# ESP_Board.net
KiCad netlist of a schematic drawn in Altium Designer
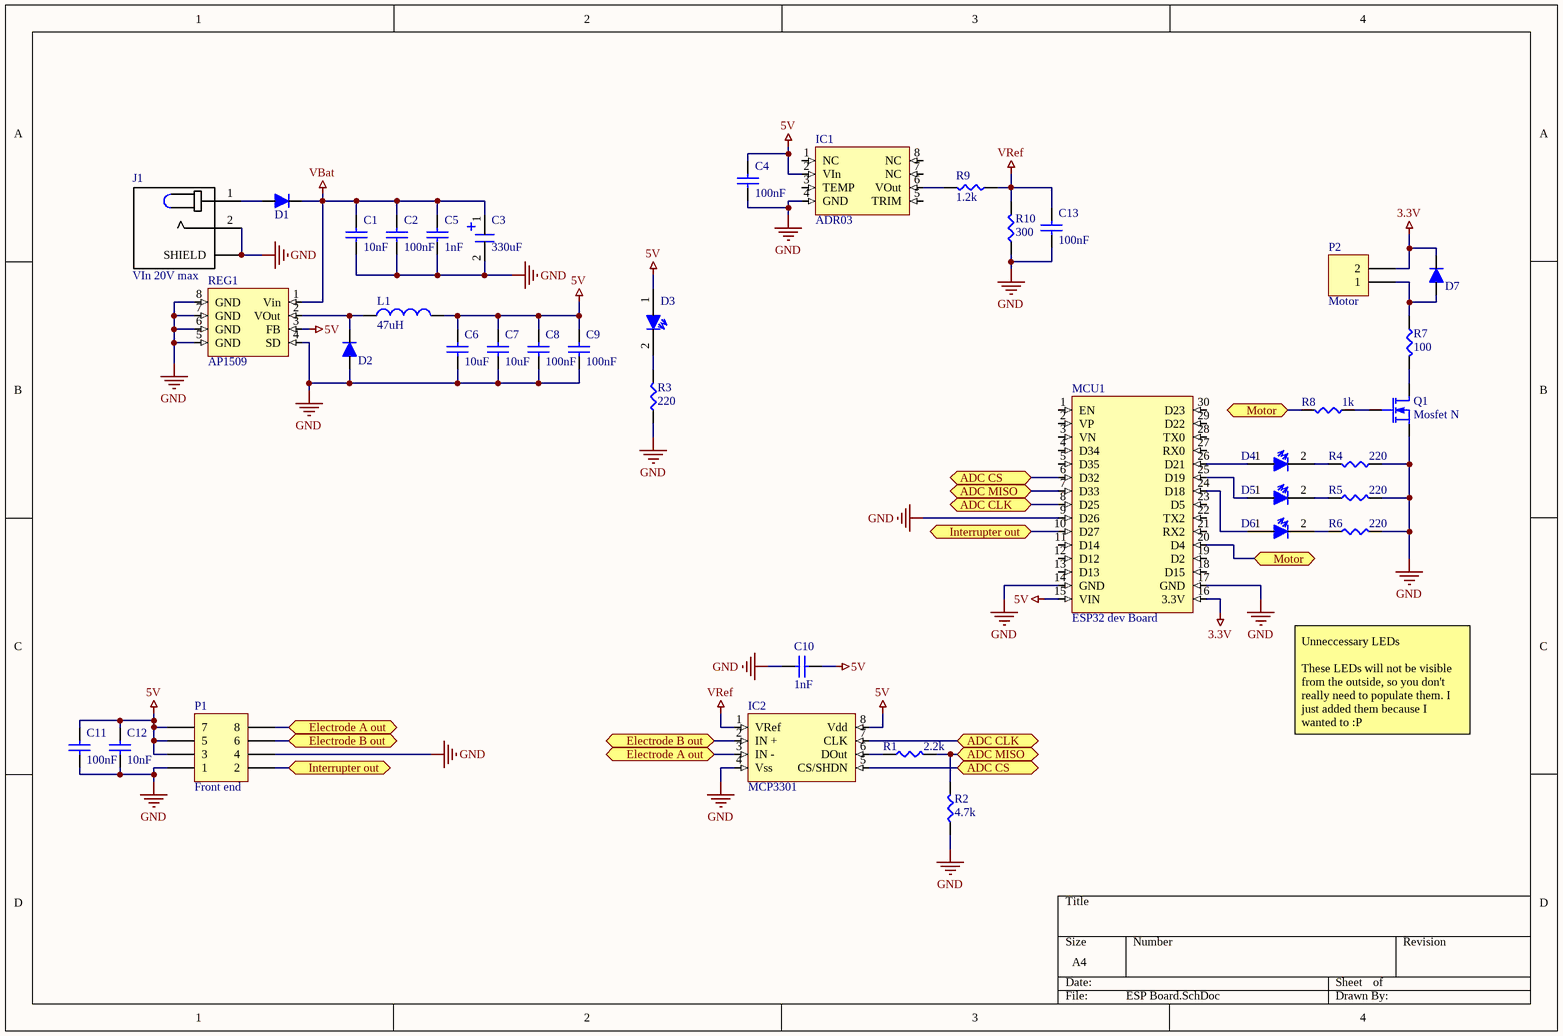
[diagram p0: ESP Board.SchDoc]

(export (version "E")
  (design (tool "Eeschema 10.0.6"))
  (components
    (comp (ref "C1") (value "10nF") (footprint "0805") (libsource (lib "stdLib") (part "Cap")))
    (comp (ref "C2") (value "100nF") (footprint "0805") (libsource (lib "stdLib") (part "Cap")))
    (comp (ref "C3")
      (value "330uF")
      (footprint "ESL476M100AH9AA")
      (libsource (lib "stdLib") (part "Cap Polar"))
    )
    (comp (ref "C4") (value "100nF") (footprint "0805") (libsource (lib "stdLib") (part "Cap")))
    (comp (ref "C5") (value "1nF") (footprint "0805") (libsource (lib "stdLib") (part "Cap")))
    (comp (ref "C6") (value "10uF") (footprint "0805") (libsource (lib "stdLib") (part "Cap")))
    (comp (ref "C7") (value "10uF") (footprint "0805") (libsource (lib "stdLib") (part "Cap")))
    (comp (ref "C8") (value "100nF") (footprint "0805") (libsource (lib "stdLib") (part "Cap")))
    (comp (ref "C9") (value "100nF") (footprint "0805") (libsource (lib "stdLib") (part "Cap")))
    (comp (ref "C10") (value "1nF") (footprint "0805") (libsource (lib "stdLib") (part "Cap")))
    (comp (ref "C11") (value "100nF") (footprint "0805") (libsource (lib "stdLib") (part "Cap")))
    (comp (ref "C12") (value "10nF") (footprint "0805") (libsource (lib "stdLib") (part "Cap")))
    (comp (ref "C13") (value "100nF") (footprint "0805") (libsource (lib "stdLib") (part "Cap")))
    (comp (ref "D1")
      (value "Diode")
      (footprint "DO-214")
      (description "Cmon its a diode what more do I need to say?")
      (libsource (lib "stdLib") (part "Diode"))
    )
    (comp (ref "D2")
      (value "Diode")
      (footprint "DO-214")
      (description "Cmon its a diode what more do I need to say?")
      (libsource (lib "stdLib") (part "Diode"))
    )
    (comp (ref "D3") (value "Power") (footprint "0805") (libsource (lib "stdLib") (part "LED")))
    (comp (ref "D4") (value "NOP") (footprint "0805") (libsource (lib "stdLib") (part "LED")))
    (comp (ref "D5") (value "NOP") (footprint "0805") (libsource (lib "stdLib") (part "LED")))
    (comp (ref "D6") (value "NOP") (footprint "0805") (libsource (lib "stdLib") (part "LED")))
    (comp (ref "D7")
      (value "Diode")
      (footprint "DO-214")
      (description "Cmon its a diode what more do I need to say?")
      (libsource (lib "stdLib") (part "Diode"))
    )
    (comp (ref "IC1")
      (value "ADR03")
      (footprint "SOIC8")
      (description "Precision voltage reference 0.1%")
      (libsource (lib "stdLib") (part "ADR0X"))
    )
    (comp (ref "IC2")
      (value "MCP3301")
      (footprint "SOIC8")
      (description "13 bit differential ADC")
      (libsource (lib "stdLib") (part "MCP3301"))
    )
    (comp (ref "J1")
      (value "VIn 20V max")
      (footprint "PJ-082BH")
      (libsource (lib "stdLib") (part "Barrel Power Plug"))
    )
    (comp (ref "L1")
      (value "47uH")
      (footprint "1812 Low density")
      (libsource (lib "stdLib") (part "Inductor"))
    )
    (comp (ref "MCU1")
      (value "ESP32 dev Board")
      (footprint "ESP32 dev board")
      (description "Dev board of the esp32")
      (libsource (lib "stdLib") (part "ESP32 dev Board"))
    )
    (comp (ref "P1")
      (value "Front end")
      (footprint "HDR2X4")
      (description "Header, 4-Pin, Dual row")
      (fields (field (name "PUBLISHER") "Altium Limited"))
      (libsource (lib "Miscellaneous Connectors") (part "Header 4X2"))
    )
    (comp (ref "P2")
      (value "Motor")
      (footprint "XH2")
      (description "Header, 2-Pin")
      (fields (field (name "PUBLISHER") "Altium Limited"))
      (libsource (lib "Miscellaneous Connectors") (part "Header 2"))
    )
    (comp (ref "Q1") (value "Mosfet N") (footprint "sot 23") (libsource (lib "stdLib") (part "Mosfet N")))
    (comp (ref "R1") (value "2.2k") (footprint "0805") (libsource (lib "stdLib") (part "Resistor")))
    (comp (ref "R2") (value "4.7k") (footprint "0805") (libsource (lib "stdLib") (part "Resistor")))
    (comp (ref "R3") (value "220") (footprint "0805") (libsource (lib "stdLib") (part "Resistor")))
    (comp (ref "R4") (value "220") (footprint "0805") (libsource (lib "stdLib") (part "Resistor")))
    (comp (ref "R5") (value "220") (footprint "0805") (libsource (lib "stdLib") (part "Resistor")))
    (comp (ref "R6") (value "220") (footprint "0805") (libsource (lib "stdLib") (part "Resistor")))
    (comp (ref "R7") (value "100") (footprint "0805") (libsource (lib "stdLib") (part "Resistor")))
    (comp (ref "R8") (value "1k") (footprint "0805") (libsource (lib "stdLib") (part "Resistor")))
    (comp (ref "R9") (value "1.2k") (footprint "0805") (libsource (lib "stdLib") (part "Resistor")))
    (comp (ref "R10") (value "300") (footprint "0805") (libsource (lib "stdLib") (part "Resistor")))
    (comp (ref "REG1")
      (value "AP1509")
      (footprint "SOIC8")
      (description "Fixed voltage buck regulator")
      (libsource (lib "stdLib") (part "AP1509"))
    )
  )
  (nets
    (net (code "1") (name "/ADC CLK") (class "Default")
      (node (ref "IC2") (pin "7") (pinfunction "CLK_7") (pintype "input"))
      (node (ref "MCU1") (pin "8") (pinfunction "D25_8") (pintype "input"))
    )
    (net (code "2") (name "/ADC CS") (class "Default")
      (node (ref "IC2") (pin "5") (pinfunction "CS/SHDN_5") (pintype "input"))
      (node (ref "MCU1") (pin "6") (pinfunction "D32_6") (pintype "input"))
    )
    (net (code "3") (name "/ADC MISO") (class "Default")
      (node (ref "MCU1") (pin "7") (pinfunction "D33_7") (pintype "input"))
      (node (ref "R1") (pin "2") (pinfunction "2_2") (pintype "passive"))
      (node (ref "R2") (pin "2") (pinfunction "2_2") (pintype "passive"))
    )
    (net (code "4") (name "/Electrode A out") (class "Default")
      (node (ref "IC2") (pin "3") (pinfunction "IN_-_3") (pintype "input"))
      (node (ref "P1") (pin "8") (pinfunction "8_8") (pintype "passive"))
    )
    (net (code "5") (name "/Electrode B out") (class "Default")
      (node (ref "IC2") (pin "2") (pinfunction "IN_+_2") (pintype "input"))
      (node (ref "P1") (pin "6") (pinfunction "6_6") (pintype "passive"))
    )
    (net (code "6") (name "/Interrupter out") (class "Default")
      (node (ref "MCU1") (pin "10") (pinfunction "D27_10") (pintype "input"))
      (node (ref "P1") (pin "2") (pinfunction "2_2") (pintype "passive"))
    )
    (net (code "7") (name "/Motor") (class "Default")
      (node (ref "MCU1") (pin "20") (pinfunction "D4_20") (pintype "input"))
      (node (ref "R8") (pin "2") (pinfunction "2_2") (pintype "passive"))
    )
    (net (code "8") (name "3.3V") (class "Default")
      (node (ref "D7") (pin "2") (pintype "passive"))
      (node (ref "MCU1") (pin "16") (pinfunction "3.3V_16") (pintype "input"))
      (node (ref "P2") (pin "2") (pinfunction "2_2") (pintype "passive"))
    )
    (net (code "9") (name "5V") (class "Default")
      (node (ref "C10") (pin "2") (pinfunction "2_2") (pintype "passive"))
      (node (ref "C11") (pin "2") (pinfunction "2_2") (pintype "passive"))
      (node (ref "C12") (pin "2") (pinfunction "2_2") (pintype "passive"))
      (node (ref "C4") (pin "2") (pinfunction "2_2") (pintype "passive"))
      (node (ref "C6") (pin "1") (pinfunction "1_1") (pintype "passive"))
      (node (ref "C7") (pin "1") (pinfunction "1_1") (pintype "passive"))
      (node (ref "C8") (pin "1") (pinfunction "1_1") (pintype "passive"))
      (node (ref "C9") (pin "1") (pinfunction "1_1") (pintype "passive"))
      (node (ref "D3") (pin "1") (pintype "passive"))
      (node (ref "IC1") (pin "2") (pinfunction "VIn_2") (pintype "input"))
      (node (ref "IC2") (pin "8") (pinfunction "Vdd_8") (pintype "input"))
      (node (ref "L1") (pin "1") (pinfunction "1_1") (pintype "passive"))
      (node (ref "MCU1") (pin "15") (pinfunction "VIN_15") (pintype "input"))
      (node (ref "P1") (pin "3") (pinfunction "3_3") (pintype "passive"))
      (node (ref "P1") (pin "5") (pinfunction "5_5") (pintype "passive"))
      (node (ref "P1") (pin "7") (pinfunction "7_7") (pintype "passive"))
      (node (ref "REG1") (pin "3") (pinfunction "FB_3") (pintype "input"))
    )
    (net (code "10") (name "GND") (class "Default")
      (node (ref "C1") (pin "1") (pinfunction "1_1") (pintype "passive"))
      (node (ref "C10") (pin "1") (pinfunction "1_1") (pintype "passive"))
      (node (ref "C11") (pin "1") (pinfunction "1_1") (pintype "passive"))
      (node (ref "C12") (pin "1") (pinfunction "1_1") (pintype "passive"))
      (node (ref "C13") (pin "1") (pinfunction "1_1") (pintype "passive"))
      (node (ref "C2") (pin "1") (pinfunction "1_1") (pintype "passive"))
      (node (ref "C3") (pin "2") (pintype "passive"))
      (node (ref "C4") (pin "1") (pinfunction "1_1") (pintype "passive"))
      (node (ref "C5") (pin "1") (pinfunction "1_1") (pintype "passive"))
      (node (ref "C6") (pin "2") (pinfunction "2_2") (pintype "passive"))
      (node (ref "C7") (pin "2") (pinfunction "2_2") (pintype "passive"))
      (node (ref "C8") (pin "2") (pinfunction "2_2") (pintype "passive"))
      (node (ref "C9") (pin "2") (pinfunction "2_2") (pintype "passive"))
      (node (ref "D2") (pin "1") (pintype "passive"))
      (node (ref "IC1") (pin "4") (pinfunction "GND_4") (pintype "input"))
      (node (ref "IC2") (pin "4") (pinfunction "Vss_4") (pintype "input"))
      (node (ref "J1") (pin "2") (pinfunction "2_2") (pintype "passive"))
      (node (ref "J1") (pin "3") (pinfunction "SHIELD_3") (pintype "passive"))
      (node (ref "J1") (pin "4") (pinfunction "SHIELD_4") (pintype "passive"))
      (node (ref "J1") (pin "5") (pinfunction "SHIELD_5") (pintype "passive"))
      (node (ref "J1") (pin "6") (pinfunction "SHIELD_6") (pintype "passive"))
      (node (ref "MCU1") (pin "14") (pinfunction "GND_14") (pintype "input"))
      (node (ref "MCU1") (pin "17") (pinfunction "GND_17") (pintype "input"))
      (node (ref "MCU1") (pin "9") (pinfunction "D26_9") (pintype "input"))
      (node (ref "P1") (pin "1") (pinfunction "1_1") (pintype "passive"))
      (node (ref "P1") (pin "4") (pinfunction "4_4") (pintype "passive"))
      (node (ref "Q1") (pin "S") (pinfunction "S_S") (pintype "passive"))
      (node (ref "R10") (pin "1") (pinfunction "1_1") (pintype "passive"))
      (node (ref "R2") (pin "1") (pinfunction "1_1") (pintype "passive"))
      (node (ref "R3") (pin "1") (pinfunction "1_1") (pintype "passive"))
      (node (ref "R4") (pin "1") (pinfunction "1_1") (pintype "passive"))
      (node (ref "R5") (pin "2") (pinfunction "2_2") (pintype "passive"))
      (node (ref "R6") (pin "2") (pinfunction "2_2") (pintype "passive"))
      (node (ref "REG1") (pin "4") (pinfunction "SD_4") (pintype "input"))
      (node (ref "REG1") (pin "5") (pinfunction "GND_5") (pintype "input"))
      (node (ref "REG1") (pin "6") (pinfunction "GND_6") (pintype "input"))
      (node (ref "REG1") (pin "7") (pinfunction "GND_7") (pintype "input"))
      (node (ref "REG1") (pin "8") (pinfunction "GND_8") (pintype "input"))
    )
    (net (code "11") (name "Net-(D1-Pad1)") (class "Default")
      (node (ref "D1") (pin "1") (pintype "passive"))
      (node (ref "J1") (pin "1") (pinfunction "1_1") (pintype "passive"))
    )
    (net (code "12") (name "Net-(D3-Pad2)") (class "Default")
      (node (ref "D3") (pin "2") (pintype "passive"))
      (node (ref "R3") (pin "2") (pinfunction "2_2") (pintype "passive"))
    )
    (net (code "13") (name "Net-(D4-Pad2)") (class "Default")
      (node (ref "D4") (pin "2") (pintype "passive"))
      (node (ref "R4") (pin "2") (pinfunction "2_2") (pintype "passive"))
    )
    (net (code "14") (name "Net-(D5-Pad2)") (class "Default")
      (node (ref "D5") (pin "2") (pintype "passive"))
      (node (ref "R5") (pin "1") (pinfunction "1_1") (pintype "passive"))
    )
    (net (code "15") (name "Net-(D6-Pad2)") (class "Default")
      (node (ref "D6") (pin "2") (pintype "passive"))
      (node (ref "R6") (pin "1") (pinfunction "1_1") (pintype "passive"))
    )
    (net (code "16") (name "Net-(D7-Pad1)") (class "Default")
      (node (ref "D7") (pin "1") (pintype "passive"))
      (node (ref "P2") (pin "1") (pinfunction "1_1") (pintype "passive"))
      (node (ref "R7") (pin "1") (pinfunction "1_1") (pintype "passive"))
    )
    (net (code "17") (name "Net-(IC1-VOut)") (class "Default")
      (node (ref "IC1") (pin "6") (pinfunction "VOut_6") (pintype "input"))
      (node (ref "R9") (pin "2") (pinfunction "2_2") (pintype "passive"))
    )
    (net (code "18") (name "Net-(IC2-DOut)") (class "Default")
      (node (ref "IC2") (pin "6") (pinfunction "DOut_6") (pintype "input"))
      (node (ref "R1") (pin "1") (pinfunction "1_1") (pintype "passive"))
    )
    (net (code "19") (name "Net-(MCU1-D18)") (class "Default")
      (node (ref "D6") (pin "1") (pintype "passive"))
      (node (ref "MCU1") (pin "24") (pinfunction "D18_24") (pintype "input"))
    )
    (net (code "20") (name "Net-(MCU1-D19)") (class "Default")
      (node (ref "D5") (pin "1") (pintype "passive"))
      (node (ref "MCU1") (pin "25") (pinfunction "D19_25") (pintype "input"))
    )
    (net (code "21") (name "Net-(MCU1-D21)") (class "Default")
      (node (ref "D4") (pin "1") (pintype "passive"))
      (node (ref "MCU1") (pin "26") (pinfunction "D21_26") (pintype "input"))
    )
    (net (code "22") (name "Net-(Q1-PadD)") (class "Default")
      (node (ref "Q1") (pin "D") (pinfunction "D_D") (pintype "passive"))
      (node (ref "R7") (pin "2") (pinfunction "2_2") (pintype "passive"))
    )
    (net (code "23") (name "Net-(Q1-PadG)") (class "Default")
      (node (ref "Q1") (pin "G") (pinfunction "G_G") (pintype "passive"))
      (node (ref "R8") (pin "1") (pinfunction "1_1") (pintype "passive"))
    )
    (net (code "24") (name "Net-(REG1-VOut)") (class "Default")
      (node (ref "D2") (pin "2") (pintype "passive"))
      (node (ref "L1") (pin "2") (pinfunction "2_2") (pintype "passive"))
      (node (ref "REG1") (pin "2") (pinfunction "VOut_2") (pintype "input"))
    )
    (net (code "25") (name "VBat") (class "Default")
      (node (ref "C1") (pin "2") (pinfunction "2_2") (pintype "passive"))
      (node (ref "C2") (pin "2") (pinfunction "2_2") (pintype "passive"))
      (node (ref "C3") (pin "1") (pintype "passive"))
      (node (ref "C5") (pin "2") (pinfunction "2_2") (pintype "passive"))
      (node (ref "D1") (pin "2") (pintype "passive"))
      (node (ref "REG1") (pin "1") (pinfunction "Vin_1") (pintype "input"))
    )
    (net (code "26") (name "VRef") (class "Default")
      (node (ref "C13") (pin "2") (pinfunction "2_2") (pintype "passive"))
      (node (ref "IC2") (pin "1") (pinfunction "VRef_1") (pintype "input"))
      (node (ref "R10") (pin "2") (pinfunction "2_2") (pintype "passive"))
      (node (ref "R9") (pin "1") (pinfunction "1_1") (pintype "passive"))
    )
    (net (code "27") (name "unconnected-(IC1-NC-Pad1)") (class "Default")
      (node (ref "IC1") (pin "1") (pinfunction "NC_1") (pintype "input"))
    )
    (net (code "28") (name "unconnected-(IC1-NC-Pad7)") (class "Default")
      (node (ref "IC1") (pin "7") (pinfunction "NC_7") (pintype "input"))
    )
    (net (code "29") (name "unconnected-(IC1-NC-Pad8)") (class "Default")
      (node (ref "IC1") (pin "8") (pinfunction "NC_8") (pintype "input"))
    )
    (net (code "30") (name "unconnected-(IC1-TEMP-Pad3)") (class "Default")
      (node (ref "IC1") (pin "3") (pinfunction "TEMP_3") (pintype "input"))
    )
    (net (code "31") (name "unconnected-(IC1-TRIM-Pad5)") (class "Default")
      (node (ref "IC1") (pin "5") (pinfunction "TRIM_5") (pintype "input"))
    )
    (net (code "32") (name "unconnected-(MCU1-D2-Pad19)") (class "Default")
      (node (ref "MCU1") (pin "19") (pinfunction "D2_19") (pintype "input"))
    )
    (net (code "33") (name "unconnected-(MCU1-D5-Pad23)") (class "Default")
      (node (ref "MCU1") (pin "23") (pinfunction "D5_23") (pintype "input"))
    )
    (net (code "34") (name "unconnected-(MCU1-D12-Pad12)") (class "Default")
      (node (ref "MCU1") (pin "12") (pinfunction "D12_12") (pintype "input"))
    )
    (net (code "35") (name "unconnected-(MCU1-D13-Pad13)") (class "Default")
      (node (ref "MCU1") (pin "13") (pinfunction "D13_13") (pintype "input"))
    )
    (net (code "36") (name "unconnected-(MCU1-D14-Pad11)") (class "Default")
      (node (ref "MCU1") (pin "11") (pinfunction "D14_11") (pintype "input"))
    )
    (net (code "37") (name "unconnected-(MCU1-D15-Pad18)") (class "Default")
      (node (ref "MCU1") (pin "18") (pinfunction "D15_18") (pintype "input"))
    )
    (net (code "38") (name "unconnected-(MCU1-D22-Pad29)") (class "Default")
      (node (ref "MCU1") (pin "29") (pinfunction "D22_29") (pintype "input"))
    )
    (net (code "39") (name "unconnected-(MCU1-D23-Pad30)") (class "Default")
      (node (ref "MCU1") (pin "30") (pinfunction "D23_30") (pintype "input"))
    )
    (net (code "40") (name "unconnected-(MCU1-D34-Pad4)") (class "Default")
      (node (ref "MCU1") (pin "4") (pinfunction "D34_4") (pintype "input"))
    )
    (net (code "41") (name "unconnected-(MCU1-D35-Pad5)") (class "Default")
      (node (ref "MCU1") (pin "5") (pinfunction "D35_5") (pintype "input"))
    )
    (net (code "42") (name "unconnected-(MCU1-EN-Pad1)") (class "Default")
      (node (ref "MCU1") (pin "1") (pinfunction "EN_1") (pintype "input"))
    )
    (net (code "43") (name "unconnected-(MCU1-RX0-Pad27)") (class "Default")
      (node (ref "MCU1") (pin "27") (pinfunction "RX0_27") (pintype "input"))
    )
    (net (code "44") (name "unconnected-(MCU1-RX2-Pad21)") (class "Default")
      (node (ref "MCU1") (pin "21") (pinfunction "RX2_21") (pintype "input"))
    )
    (net (code "45") (name "unconnected-(MCU1-TX0-Pad28)") (class "Default")
      (node (ref "MCU1") (pin "28") (pinfunction "TX0_28") (pintype "input"))
    )
    (net (code "46") (name "unconnected-(MCU1-TX2-Pad22)") (class "Default")
      (node (ref "MCU1") (pin "22") (pinfunction "TX2_22") (pintype "input"))
    )
    (net (code "47") (name "unconnected-(MCU1-VN-Pad3)") (class "Default")
      (node (ref "MCU1") (pin "3") (pinfunction "VN_3") (pintype "input"))
    )
    (net (code "48") (name "unconnected-(MCU1-VP-Pad2)") (class "Default")
      (node (ref "MCU1") (pin "2") (pinfunction "VP_2") (pintype "input"))
    )
  )
)
